# 3-1.net
KiCad netlist of a schematic drawn in Altium Designer
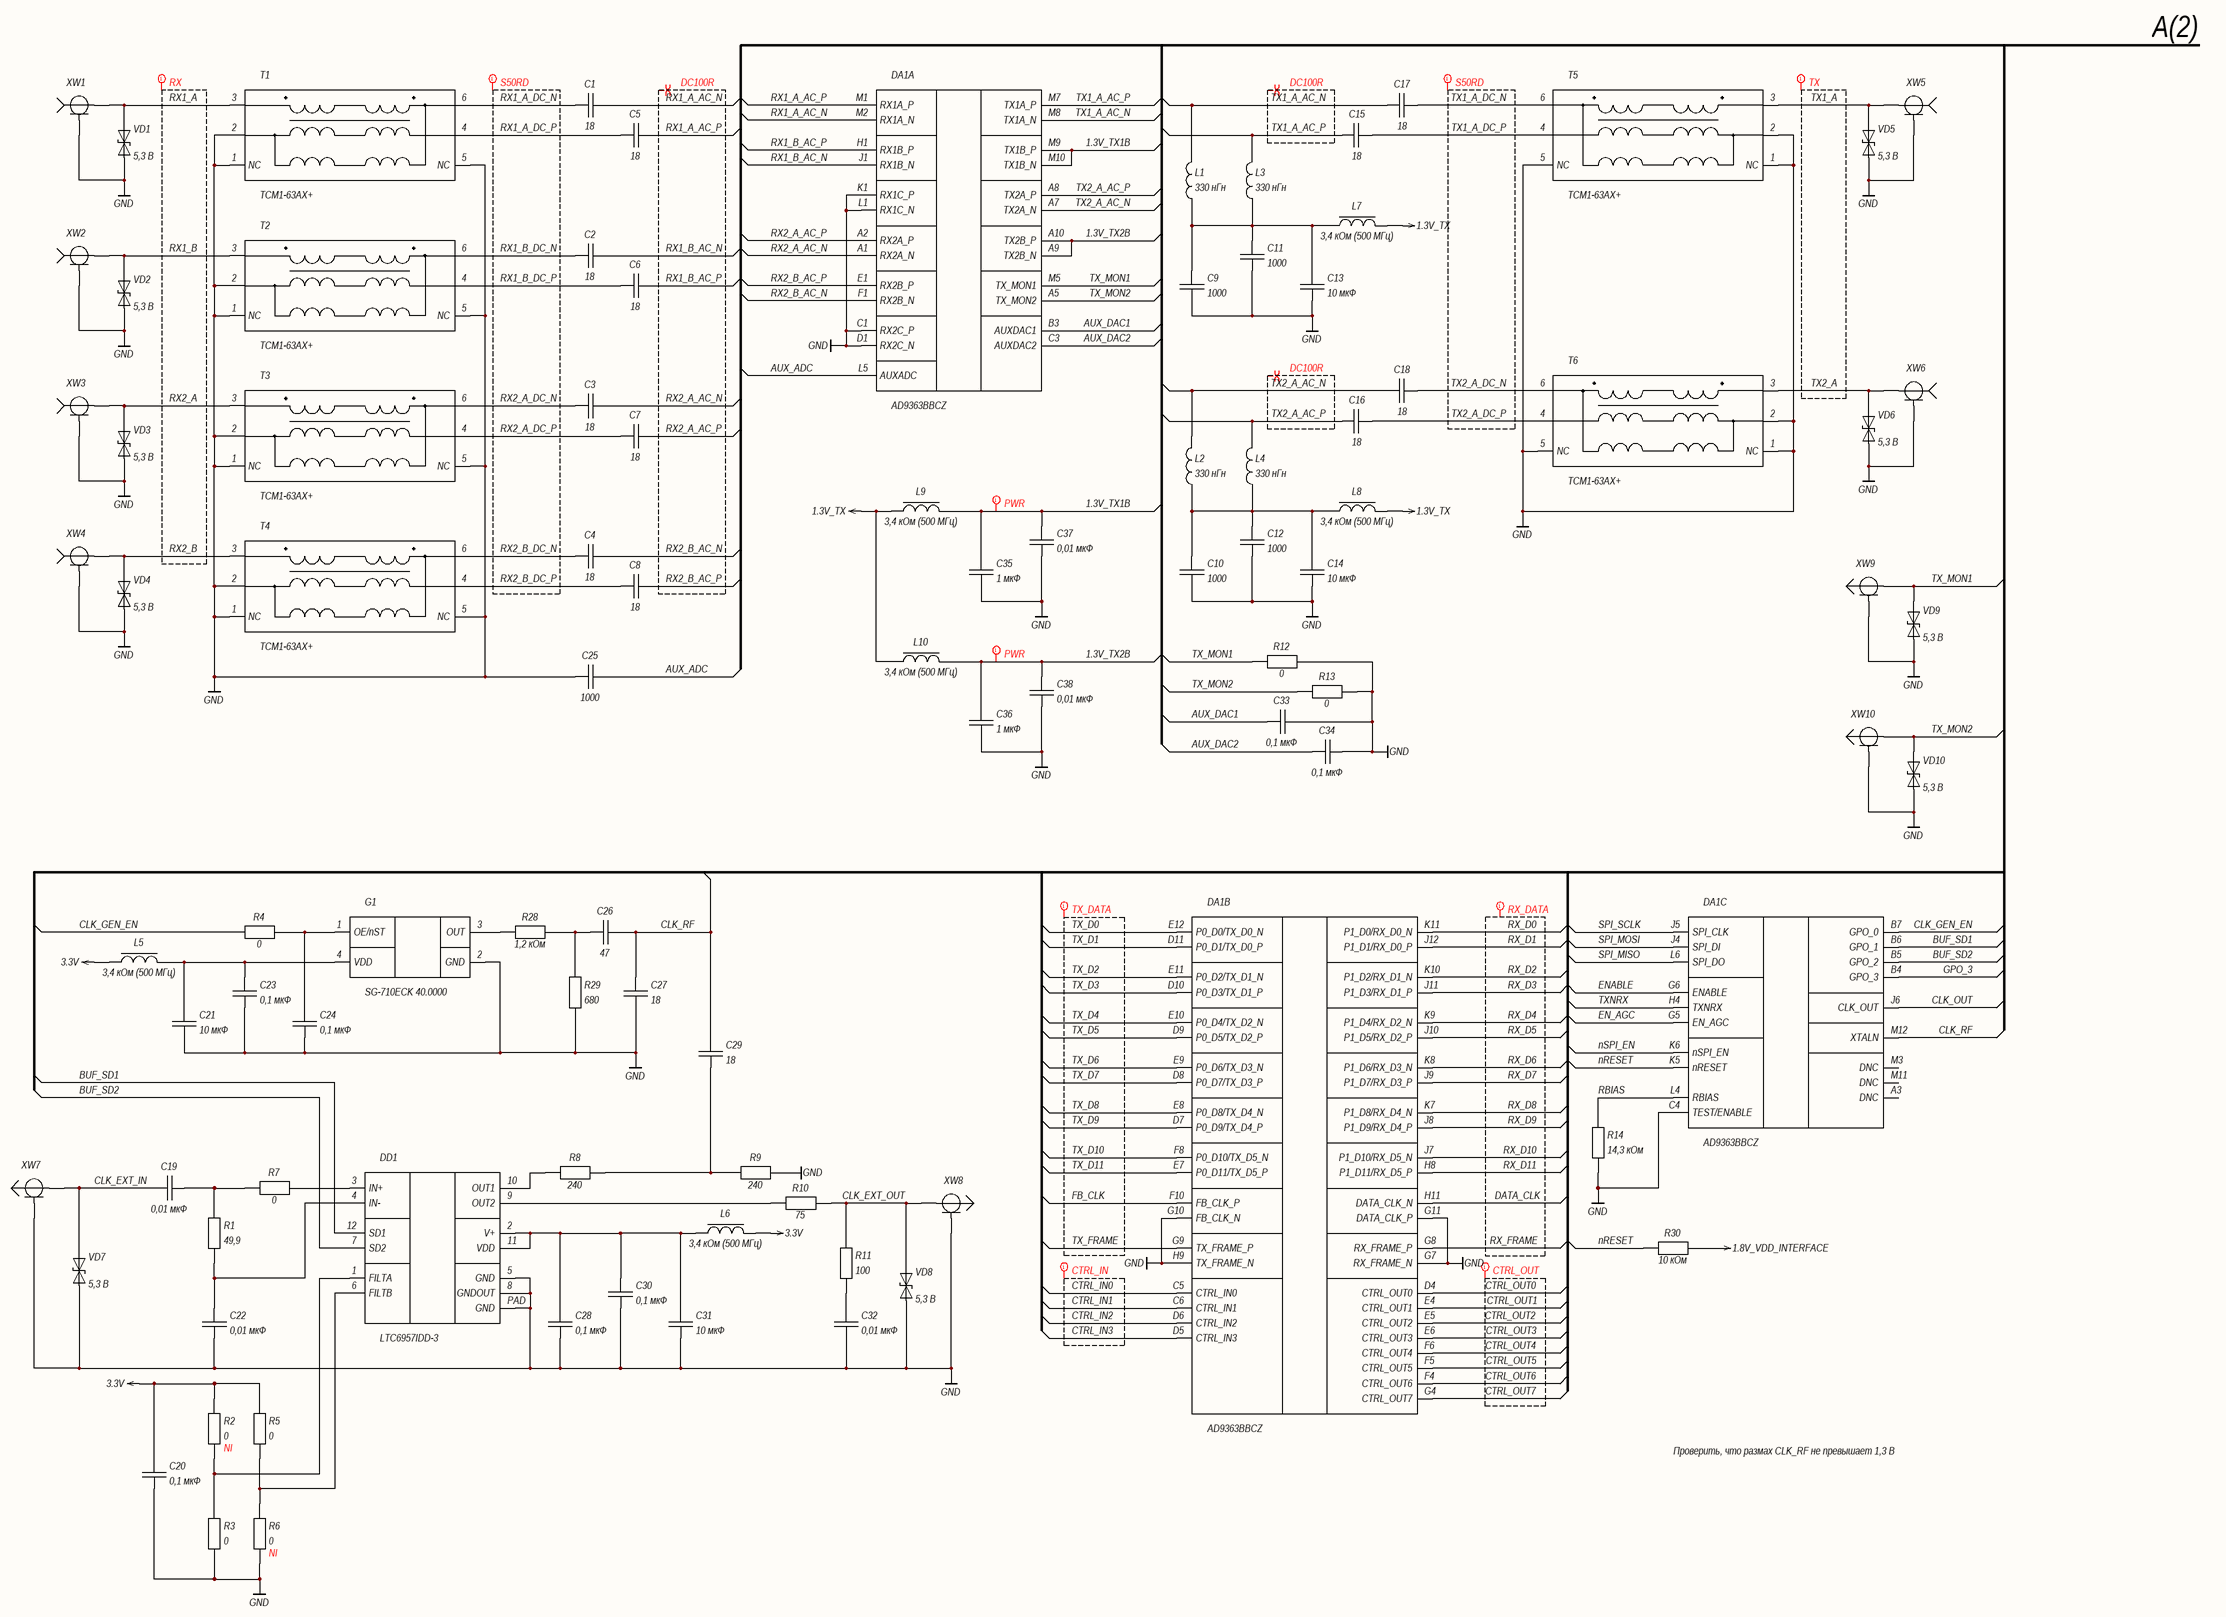
[diagram p0: Э3-1.SchDoc]

(export (version "E")
  (design (tool "Eeschema 10.0.6"))
  (components
    (comp (ref "C1")
      (value "18")
      (footprint "C0201-B-0.3mm-NO")
      (description "0201 18 пФ ±5% 50 В C0G")
      (fields (field (name "PARTNUMBER") "GRM0335C1H180JA01D"))
      (libsource (lib "Capacitors") (part "Non Polar Hor."))
    )
    (comp (ref "C2")
      (value "18")
      (footprint "C0201-B-0.3mm-NO")
      (description "0201 18 пФ ±5% 50 В C0G")
      (fields (field (name "PARTNUMBER") "GRM0335C1H180JA01D"))
      (libsource (lib "Capacitors") (part "Non Polar Hor."))
    )
    (comp (ref "C3")
      (value "18")
      (footprint "C0201-B-0.3mm-NO")
      (description "0201 18 пФ ±5% 50 В C0G")
      (fields (field (name "PARTNUMBER") "GRM0335C1H180JA01D"))
      (libsource (lib "Capacitors") (part "Non Polar Hor."))
    )
    (comp (ref "C4")
      (value "18")
      (footprint "C0201-B-0.3mm-NO")
      (description "0201 18 пФ ±5% 50 В C0G")
      (fields (field (name "PARTNUMBER") "GRM0335C1H180JA01D"))
      (libsource (lib "Capacitors") (part "Non Polar Hor."))
    )
    (comp (ref "C5")
      (value "18")
      (footprint "C0201-B-0.3mm-NO")
      (description "0201 18 пФ ±5% 50 В C0G")
      (fields (field (name "PARTNUMBER") "GRM0335C1H180JA01D"))
      (libsource (lib "Capacitors") (part "Non Polar Hor."))
    )
    (comp (ref "C6")
      (value "18")
      (footprint "C0201-B-0.3mm-NO")
      (description "0201 18 пФ ±5% 50 В C0G")
      (fields (field (name "PARTNUMBER") "GRM0335C1H180JA01D"))
      (libsource (lib "Capacitors") (part "Non Polar Hor."))
    )
    (comp (ref "C7")
      (value "18")
      (footprint "C0201-B-0.3mm-NO")
      (description "0201 18 пФ ±5% 50 В C0G")
      (fields (field (name "PARTNUMBER") "GRM0335C1H180JA01D"))
      (libsource (lib "Capacitors") (part "Non Polar Hor."))
    )
    (comp (ref "C8")
      (value "18")
      (footprint "C0201-B-0.3mm-NO")
      (description "0201 18 пФ ±5% 50 В C0G")
      (fields (field (name "PARTNUMBER") "GRM0335C1H180JA01D"))
      (libsource (lib "Capacitors") (part "Non Polar Hor."))
    )
    (comp (ref "C9")
      (value "1000")
      (footprint "C0201-B-0.3mm-NO")
      (description "0201 1000 пФ ±10% 16 В X7R")
      (libsource (lib "Capacitors") (part "Non Polar Ver."))
    )
    (comp (ref "C10")
      (value "1000")
      (footprint "C0201-B-0.3mm-NO")
      (description "0201 1000 пФ ±10% 16 В X7R")
      (libsource (lib "Capacitors") (part "Non Polar Ver."))
    )
    (comp (ref "C11")
      (value "1000")
      (footprint "C0201-B-0.3mm-NO")
      (description "0201 1000 пФ ±10% 16 В X7R")
      (libsource (lib "Capacitors") (part "Non Polar Ver."))
    )
    (comp (ref "C12")
      (value "1000")
      (footprint "C0201-B-0.3mm-NO")
      (description "0201 1000 пФ ±10% 16 В X7R")
      (libsource (lib "Capacitors") (part "Non Polar Ver."))
    )
    (comp (ref "C13")
      (value "10 мкФ")
      (footprint "C0603-B-0.8mm-NO")
      (description "0603 10 мкФ ±10% 16 В X7R")
      (libsource (lib "Capacitors") (part "Non Polar Ver."))
    )
    (comp (ref "C14")
      (value "10 мкФ")
      (footprint "C0603-B-0.8mm-NO")
      (description "0603 10 мкФ ±10% 16 В X7R")
      (libsource (lib "Capacitors") (part "Non Polar Ver."))
    )
    (comp (ref "C15")
      (value "18")
      (footprint "C0201-B-0.3mm-NO")
      (description "0201 18 пФ ±5% 50 В C0G")
      (fields (field (name "PARTNUMBER") "GRM0335C1H180JA01D"))
      (libsource (lib "Capacitors") (part "Non Polar Hor."))
    )
    (comp (ref "C16")
      (value "18")
      (footprint "C0201-B-0.3mm-NO")
      (description "0201 18 пФ ±5% 50 В C0G")
      (fields (field (name "PARTNUMBER") "GRM0335C1H180JA01D"))
      (libsource (lib "Capacitors") (part "Non Polar Hor."))
    )
    (comp (ref "C17")
      (value "18")
      (footprint "C0201-B-0.3mm-NO")
      (description "0201 18 пФ ±5% 50 В C0G")
      (fields (field (name "PARTNUMBER") "GRM0335C1H180JA01D"))
      (libsource (lib "Capacitors") (part "Non Polar Hor."))
    )
    (comp (ref "C18")
      (value "18")
      (footprint "C0201-B-0.3mm-NO")
      (description "0201 18 пФ ±5% 50 В C0G")
      (fields (field (name "PARTNUMBER") "GRM0335C1H180JA01D"))
      (libsource (lib "Capacitors") (part "Non Polar Hor."))
    )
    (comp (ref "C19")
      (value "0,01 мкФ")
      (footprint "C0201-B-0.3mm-NO")
      (description "0201 0,01 мкФ ±10% 16 В X7R")
      (fields (field (name "PARTNUMBER") "GRM0335C1H180JA01D"))
      (libsource (lib "Capacitors") (part "Non Polar Hor."))
    )
    (comp (ref "C20")
      (value "0,1 мкФ")
      (footprint "C0402-B-0.5mm-NO")
      (description "0402 0,1 мкФ ±10% 16 В X7R")
      (libsource (lib "Capacitors") (part "Non Polar Ver."))
    )
    (comp (ref "C21")
      (value "10 мкФ")
      (footprint "C0603-B-0.8mm-NO")
      (description "0603 10 мкФ ±10% 16 В X7R")
      (libsource (lib "Capacitors") (part "Non Polar Ver."))
    )
    (comp (ref "C22")
      (value "0,01 мкФ")
      (footprint "C0201-B-0.3mm-NO")
      (description "0201 0,01 мкФ ±10% 16 В X7R")
      (libsource (lib "Capacitors") (part "Non Polar Ver."))
    )
    (comp (ref "C23")
      (value "0,1 мкФ")
      (footprint "C0402-B-0.5mm-NO")
      (description "0402 0,1 мкФ ±10% 16 В X7R")
      (libsource (lib "Capacitors") (part "Non Polar Ver."))
    )
    (comp (ref "C24")
      (value "0,1 мкФ")
      (footprint "C0402-B-0.5mm-NO")
      (description "0402 0,1 мкФ ±10% 16 В X7R")
      (libsource (lib "Capacitors") (part "Non Polar Ver."))
    )
    (comp (ref "C25")
      (value "1000")
      (footprint "C0201-B-0.3mm-NO")
      (description "0201 1000 пФ ±10% 16 В X7R")
      (libsource (lib "Capacitors") (part "Non Polar Hor."))
    )
    (comp (ref "C26")
      (value "47")
      (footprint "C0402-B-0.5mm-NO")
      (description "0402 47 пФ ±5% 50 В X7R")
      (fields (field (name "PARTNUMBER") "GRM0335C1H180JA01D"))
      (libsource (lib "Capacitors") (part "Non Polar Hor."))
    )
    (comp (ref "C27")
      (value "18")
      (footprint "C0201-B-0.3mm-NO")
      (description "0201 18 пФ ±5% 50 В C0G")
      (libsource (lib "Capacitors") (part "Non Polar Ver."))
    )
    (comp (ref "C28")
      (value "0,1 мкФ")
      (footprint "C0402-B-0.5mm-NO")
      (description "0402 0,1 мкФ ±10% 16 В X7R")
      (libsource (lib "Capacitors") (part "Non Polar Ver."))
    )
    (comp (ref "C29")
      (value "18")
      (footprint "C0201-B-0.3mm-NO")
      (description "0201 18 пФ ±5% 50 В C0G")
      (libsource (lib "Capacitors") (part "Non Polar Ver."))
    )
    (comp (ref "C30")
      (value "0,1 мкФ")
      (footprint "C0402-B-0.5mm-NO")
      (description "0402 0,1 мкФ ±10% 16 В X7R")
      (libsource (lib "Capacitors") (part "Non Polar Ver."))
    )
    (comp (ref "C31")
      (value "10 мкФ")
      (footprint "C0603-B-0.8mm-NO")
      (description "0603 10 мкФ ±10% 16 В X7R")
      (libsource (lib "Capacitors") (part "Non Polar Ver."))
    )
    (comp (ref "C32")
      (value "0,01 мкФ")
      (footprint "C0201-B-0.3mm-NO")
      (description "0201 0,01 мкФ ±10% 16 В X7R")
      (libsource (lib "Capacitors") (part "Non Polar Ver."))
    )
    (comp (ref "C33")
      (value "0,1 мкФ")
      (footprint "C0201-B-0.3mm-NO")
      (description "0201 0,1 мкФ ±10% 16 В X7R")
      (libsource (lib "Capacitors") (part "Non Polar Hor."))
    )
    (comp (ref "C34")
      (value "0,1 мкФ")
      (footprint "C0201-B-0.3mm-NO")
      (description "0201 0,1 мкФ ±10% 16 В X7R")
      (libsource (lib "Capacitors") (part "Non Polar Hor."))
    )
    (comp (ref "C35")
      (value "1 мкФ")
      (footprint "C0402-B-0.5mm-NO")
      (description "0402 1 мкФ ±10% 16 В X7R")
      (libsource (lib "Capacitors") (part "Non Polar Ver."))
    )
    (comp (ref "C36")
      (value "1 мкФ")
      (footprint "C0402-B-0.5mm-NO")
      (description "0402 1 мкФ ±10% 16 В X7R")
      (libsource (lib "Capacitors") (part "Non Polar Ver."))
    )
    (comp (ref "C37")
      (value "0,01 мкФ")
      (footprint "C0201-B-0.3mm-NO")
      (description "0201 0,01 мкФ ±10% 16 В X7R")
      (libsource (lib "Capacitors") (part "Non Polar Ver."))
    )
    (comp (ref "C38")
      (value "0,01 мкФ")
      (footprint "C0201-B-0.3mm-NO")
      (description "0201 0,01 мкФ ±10% 16 В X7R")
      (libsource (lib "Capacitors") (part "Non Polar Ver."))
    )
    (comp (ref "DA1")
      (value "AD9363BBCZ")
      (footprint "144-BGA")
      (description "RF Agile Transceiver")
      (fields (field (name "MANUFACTURER") "AnalogDevices"))
      (libsource (lib "Analog") (part "AD9363"))
    )
    (comp (ref "DD1")
      (value "LTC6957IDD-3")
      (footprint "12-DFN")
      (fields (field (name "MANUFACTURER") "AnalogDevices"))
      (libsource (lib "Digital") (part "LTC6957IDD-3"))
    )
    (comp (ref "G1")
      (value "SG-710ECK 40.0000")
      (footprint "Generator 7x5x1.3")
      (fields (field (name "TOLERANCE") "± ppm"))
      (libsource (lib "Oscilators") (part "Generator"))
    )
    (comp (ref "L1")
      (value "330 нГн")
      (footprint "LCL0805-C-1.2mm-NO")
      (fields (field (name "PARTNUMBER") "L-15WR33GV4E"))
      (libsource (lib "Inductors") (part "Inductor Ver."))
    )
    (comp (ref "L2")
      (value "330 нГн")
      (footprint "LCL0805-C-1.2mm-NO")
      (fields (field (name "PARTNUMBER") "L-15WR33GV4E"))
      (libsource (lib "Inductors") (part "Inductor Ver."))
    )
    (comp (ref "L3")
      (value "330 нГн")
      (footprint "LCL0805-C-1.2mm-NO")
      (fields (field (name "PARTNUMBER") "L-15WR33GV4E"))
      (libsource (lib "Inductors") (part "Inductor Ver."))
    )
    (comp (ref "L4")
      (value "330 нГн")
      (footprint "LCL0805-C-1.2mm-NO")
      (fields (field (name "PARTNUMBER") "L-15WR33GV4E"))
      (libsource (lib "Inductors") (part "Inductor Ver."))
    )
    (comp (ref "L5")
      (value "3,4 кОм (500 МГц)")
      (footprint "L0402-B-0.5mm")
      (fields (field (name "PARTNUMBER") "BLM15HD182BH1"))
      (libsource (lib "Inductors") (part "Inductor MC Hor."))
    )
    (comp (ref "L6")
      (value "3,4 кОм (500 МГц)")
      (footprint "L0402-B-0.5mm")
      (fields (field (name "PARTNUMBER") "BLM15HD182BH1"))
      (libsource (lib "Inductors") (part "Inductor MC Hor."))
    )
    (comp (ref "L7")
      (value "3,4 кОм (500 МГц)")
      (footprint "L0402-B-0.5mm-NO")
      (fields (field (name "PARTNUMBER") "BLM15HD182BH1"))
      (libsource (lib "Inductors") (part "Inductor MC Hor."))
    )
    (comp (ref "L8")
      (value "3,4 кОм (500 МГц)")
      (footprint "L0402-B-0.5mm-NO")
      (fields (field (name "PARTNUMBER") "BLM15HD182BH1"))
      (libsource (lib "Inductors") (part "Inductor MC Hor."))
    )
    (comp (ref "L9")
      (value "3,4 кОм (500 МГц)")
      (footprint "L0402-B-0.5mm-NO")
      (fields (field (name "PARTNUMBER") "BLM15HD182BH1"))
      (libsource (lib "Inductors") (part "Inductor MC Hor."))
    )
    (comp (ref "L10")
      (value "3,4 кОм (500 МГц)")
      (footprint "L0402-B-0.5mm-NO")
      (fields (field (name "PARTNUMBER") "BLM15HD182BH1"))
      (libsource (lib "Inductors") (part "Inductor MC Hor."))
    )
    (comp (ref "R1")
      (value "49,9")
      (footprint "CR0402-B-0.35mm-NO")
      (description "0402 49,9 Ом 1%")
      (libsource (lib "Resistors") (part "Resistor Ver."))
    )
    (comp (ref "R2")
      (value "0")
      (footprint "CR0402-B-0.35mm-NO")
      (description "0402 0 Ом")
      (fields (field (name "COMPONENTTYPE") "NI"))
      (libsource (lib "Resistors") (part "Resistor Ver."))
    )
    (comp (ref "R3")
      (value "0")
      (footprint "CR0402-B-0.35mm-NO")
      (description "0402 0 Ом")
      (libsource (lib "Resistors") (part "Resistor Ver."))
    )
    (comp (ref "R4")
      (value "0")
      (footprint "CR0402-B-0.35mm-NO")
      (description "0402 0 Ом")
      (libsource (lib "Resistors") (part "Resistor Hor."))
    )
    (comp (ref "R5")
      (value "0")
      (footprint "CR0402-B-0.35mm-NO")
      (description "0402 0 Ом")
      (libsource (lib "Resistors") (part "Resistor Ver."))
    )
    (comp (ref "R6")
      (value "0")
      (footprint "CR0402-B-0.35mm-NO")
      (description "0402 0 Ом")
      (fields (field (name "COMPONENTTYPE") "NI"))
      (libsource (lib "Resistors") (part "Resistor Ver."))
    )
    (comp (ref "R7")
      (value "0")
      (footprint "CR0402-B-0.35mm-NO")
      (description "0402 0 Ом")
      (libsource (lib "Resistors") (part "Resistor Hor."))
    )
    (comp (ref "R8")
      (value "240")
      (footprint "CR0402-B-0.35mm-NO")
      (description "0402 240 Ом ±1%")
      (libsource (lib "Resistors") (part "Resistor Hor."))
    )
    (comp (ref "R9")
      (value "240")
      (footprint "CR0402-B-0.35mm-NO")
      (description "0402 240 Ом ±1%")
      (libsource (lib "Resistors") (part "Resistor Hor."))
    )
    (comp (ref "R10")
      (value "75")
      (footprint "CR0402-B-0.35mm-NO")
      (description "0402 75 Ом ±1%")
      (libsource (lib "Resistors") (part "Resistor Hor."))
    )
    (comp (ref "R11")
      (value "100")
      (footprint "CR0402-B-0.35mm-NO")
      (description "0402 100 Ом ±1%")
      (libsource (lib "Resistors") (part "Resistor Ver."))
    )
    (comp (ref "R12")
      (value "0")
      (footprint "CR0402-B-0.35mm-NO")
      (description "0402 0 Ом")
      (libsource (lib "Resistors") (part "Resistor Hor."))
    )
    (comp (ref "R13")
      (value "0")
      (footprint "CR0402-B-0.35mm-NO")
      (description "0402 0 Ом")
      (libsource (lib "Resistors") (part "Resistor Hor."))
    )
    (comp (ref "R14")
      (value "14,3 кОм")
      (footprint "CR0402-B-0.35mm-NO")
      (description "0402 14,3 кОм ±1%")
      (libsource (lib "Resistors") (part "Resistor Ver."))
    )
    (comp (ref "R28")
      (value "1,2 кОм")
      (footprint "CR0402-B-0.35mm-NO")
      (description "0402 1,2 кОм ±1%")
      (libsource (lib "Resistors") (part "Resistor Hor."))
    )
    (comp (ref "R29")
      (value "680")
      (footprint "CR0402-B-0.35mm-NO")
      (description "0402 680 Ом ±1%")
      (libsource (lib "Resistors") (part "Resistor Ver."))
    )
    (comp (ref "R30")
      (value "10 кОм")
      (footprint "CR0402-B-0.35mm-NO")
      (description "0402 10 кОм ±5%")
      (libsource (lib "Resistors") (part "Resistor Hor."))
    )
    (comp (ref "T1")
      (value "TCM1-63AX+")
      (footprint "TCM1-63AX+")
      (fields (field (name "PARTNUMBER") "TCM1-63AX+"))
      (libsource (lib "") (part "TCM1-63AX+_1"))
    )
    (comp (ref "T2")
      (value "TCM1-63AX+")
      (footprint "TCM1-63AX+")
      (fields (field (name "PARTNUMBER") "TCM1-63AX+"))
      (libsource (lib "") (part "TCM1-63AX+_1"))
    )
    (comp (ref "T3")
      (value "TCM1-63AX+")
      (footprint "TCM1-63AX+")
      (fields (field (name "PARTNUMBER") "TCM1-63AX+"))
      (libsource (lib "") (part "TCM1-63AX+_1"))
    )
    (comp (ref "T4")
      (value "TCM1-63AX+")
      (footprint "TCM1-63AX+")
      (fields (field (name "PARTNUMBER") "TCM1-63AX+"))
      (libsource (lib "") (part "TCM1-63AX+_1"))
    )
    (comp (ref "T5")
      (value "TCM1-63AX+")
      (footprint "TCM1-63AX+")
      (fields (field (name "PARTNUMBER") "TCM1-63AX+"))
      (libsource (lib "Inductors") (part "TCM1-63AX+"))
    )
    (comp (ref "T6")
      (value "TCM1-63AX+")
      (footprint "TCM1-63AX+")
      (fields (field (name "PARTNUMBER") "TCM1-63AX+"))
      (libsource (lib "Inductors") (part "TCM1-63AX+"))
    )
    (comp (ref "VD1")
      (value "~")
      (footprint "X3DFN2-NO")
      (fields (field (name "VOLTAGE") "5,3 В") (field (name "PARTNUMBER") "ESD8472MUT5G"))
      (libsource (lib "Diodes") (part "TVS Ver."))
    )
    (comp (ref "VD2")
      (value "~")
      (footprint "X3DFN2-NO")
      (fields (field (name "VOLTAGE") "5,3 В") (field (name "PARTNUMBER") "ESD8472MUT5G"))
      (libsource (lib "Diodes") (part "TVS Ver."))
    )
    (comp (ref "VD3")
      (value "~")
      (footprint "X3DFN2-NO")
      (fields (field (name "VOLTAGE") "5,3 В") (field (name "PARTNUMBER") "ESD8472MUT5G"))
      (libsource (lib "Diodes") (part "TVS Ver."))
    )
    (comp (ref "VD4")
      (value "~")
      (footprint "X3DFN2-NO")
      (fields (field (name "VOLTAGE") "5,3 В") (field (name "PARTNUMBER") "ESD8472MUT5G"))
      (libsource (lib "Diodes") (part "TVS Ver."))
    )
    (comp (ref "VD5")
      (value "~")
      (footprint "X3DFN2-NO")
      (fields (field (name "VOLTAGE") "5,3 В") (field (name "PARTNUMBER") "ESD8472MUT5G"))
      (libsource (lib "Diodes") (part "TVS Ver."))
    )
    (comp (ref "VD6")
      (value "~")
      (footprint "X3DFN2-NO")
      (fields (field (name "VOLTAGE") "5,3 В") (field (name "PARTNUMBER") "ESD8472MUT5G"))
      (libsource (lib "Diodes") (part "TVS Ver."))
    )
    (comp (ref "VD7")
      (value "~")
      (footprint "X3DFN2-NO")
      (fields (field (name "VOLTAGE") "5,3 В") (field (name "PARTNUMBER") "ESD8472MUT5G"))
      (libsource (lib "Diodes") (part "TVS Ver."))
    )
    (comp (ref "VD8")
      (value "~")
      (footprint "X3DFN2-NO")
      (fields (field (name "VOLTAGE") "5,3 В") (field (name "PARTNUMBER") "ESD8472MUT5G"))
      (libsource (lib "Diodes") (part "TVS Ver."))
    )
    (comp (ref "VD9")
      (value "~")
      (footprint "X3DFN2-NO")
      (fields (field (name "VOLTAGE") "5,3 В") (field (name "PARTNUMBER") "ESD8472MUT5G"))
      (libsource (lib "Diodes") (part "TVS Ver."))
    )
    (comp (ref "VD10")
      (value "~")
      (footprint "X3DFN2-NO")
      (fields (field (name "VOLTAGE") "5,3 В") (field (name "PARTNUMBER") "ESD8472MUT5G"))
      (libsource (lib "Diodes") (part "TVS Ver."))
    )
    (comp (ref "XW1")
      (value "XW(S)")
      (footprint "SMA-J-P-H-ST-EM1")
      (libsource (lib "Connectors") (part "XW(S)"))
    )
    (comp (ref "XW2")
      (value "XW(S)")
      (footprint "SMA-J-P-H-ST-EM1")
      (libsource (lib "Connectors") (part "XW(S)"))
    )
    (comp (ref "XW3")
      (value "XW(S)")
      (footprint "SMA-J-P-H-ST-EM1")
      (libsource (lib "Connectors") (part "XW(S)"))
    )
    (comp (ref "XW4")
      (value "XW(S)")
      (footprint "SMA-J-P-H-ST-EM1")
      (libsource (lib "Connectors") (part "XW(S)"))
    )
    (comp (ref "XW5")
      (value "XW(S)")
      (footprint "SMA-J-P-H-ST-EM1")
      (libsource (lib "Connectors") (part "XW(S)"))
    )
    (comp (ref "XW6")
      (value "XW(S)")
      (footprint "SMA-J-P-H-ST-EM1")
      (libsource (lib "Connectors") (part "XW(S)"))
    )
    (comp (ref "XW7")
      (value "XW(P)")
      (footprint "U.FL STR PLG")
      (libsource (lib "Connectors") (part "XW(P)"))
    )
    (comp (ref "XW8")
      (value "XW(P)")
      (footprint "U.FL STR PLG")
      (libsource (lib "Connectors") (part "XW(P)"))
    )
    (comp (ref "XW9")
      (value "XW(P)")
      (footprint "U.FL STR PLG")
      (libsource (lib "Connectors") (part "XW(P)"))
    )
    (comp (ref "XW10")
      (value "XW(P)")
      (footprint "U.FL STR PLG")
      (libsource (lib "Connectors") (part "XW(P)"))
    )
  )
  (nets
    (net (code "1") (name "/1.3V_TX1B") (class "Default")
      (node (ref "C35") (pin "1") (pinfunction "1_1") (pintype "passive"))
      (node (ref "C37") (pin "1") (pinfunction "1_1") (pintype "passive"))
      (node (ref "DA1") (pin "M10") (pinfunction "TX1B_N_M10") (pintype "passive"))
      (node (ref "DA1") (pin "M9") (pinfunction "TX1B_P_M9") (pintype "passive"))
      (node (ref "L9") (pin "2") (pinfunction "2_2") (pintype "passive"))
    )
    (net (code "2") (name "/1.3V_TX2B") (class "Default")
      (node (ref "C36") (pin "1") (pinfunction "1_1") (pintype "passive"))
      (node (ref "C38") (pin "1") (pinfunction "1_1") (pintype "passive"))
      (node (ref "DA1") (pin "A10") (pinfunction "TX2B_P_A10") (pintype "passive"))
      (node (ref "DA1") (pin "A9") (pinfunction "TX2B_N_A9") (pintype "passive"))
      (node (ref "L10") (pin "2") (pinfunction "2_2") (pintype "passive"))
    )
    (net (code "3") (name "/AUX_ADC") (class "Default")
      (node (ref "C25") (pin "2") (pinfunction "2_2") (pintype "passive"))
      (node (ref "DA1") (pin "L5") (pinfunction "AUXADC_L5") (pintype "passive"))
    )
    (net (code "4") (name "/AUX_DAC1") (class "Default")
      (node (ref "C33") (pin "1") (pinfunction "1_1") (pintype "passive"))
      (node (ref "DA1") (pin "B3") (pinfunction "AUXDAC1_B3") (pintype "passive"))
    )
    (net (code "5") (name "/AUX_DAC2") (class "Default")
      (node (ref "C34") (pin "1") (pinfunction "1_1") (pintype "passive"))
      (node (ref "DA1") (pin "C3") (pinfunction "AUXDAC2_C3") (pintype "passive"))
    )
    (net (code "6") (name "/BUF_SD1") (class "Default")
      (node (ref "DA1") (pin "B6") (pinfunction "GPO_1_B6") (pintype "passive"))
      (node (ref "DD1") (pin "12") (pinfunction "SD1_12") (pintype "passive"))
    )
    (net (code "7") (name "/BUF_SD2") (class "Default")
      (node (ref "DA1") (pin "B5") (pinfunction "GPO_2_B5") (pintype "passive"))
      (node (ref "DD1") (pin "7") (pinfunction "SD2_7") (pintype "passive"))
    )
    (net (code "8") (name "/CLK_EXT_IN") (class "Default")
      (node (ref "C19") (pin "1") (pinfunction "1_1") (pintype "passive"))
      (node (ref "VD7") (pin "1") (pinfunction "1_1") (pintype "passive"))
      (node (ref "XW7") (pin "1") (pinfunction "1_1") (pintype "passive"))
    )
    (net (code "9") (name "/CLK_EXT_OUT") (class "Default")
      (node (ref "R10") (pin "2") (pinfunction "2_2") (pintype "passive"))
      (node (ref "R11") (pin "1") (pinfunction "1_1") (pintype "passive"))
      (node (ref "VD8") (pin "1") (pinfunction "1_1") (pintype "passive"))
      (node (ref "XW8") (pin "1") (pinfunction "1_1") (pintype "passive"))
    )
    (net (code "10") (name "/CLK_GEN_EN") (class "Default")
      (node (ref "DA1") (pin "B7") (pinfunction "GPO_0_B7") (pintype "passive"))
      (node (ref "R4") (pin "1") (pinfunction "1_1") (pintype "passive"))
    )
    (net (code "11") (name "/CLK_OUT") (class "Default")
      (node (ref "DA1") (pin "J6") (pinfunction "CLK_OUT_J6") (pintype "passive"))
    )
    (net (code "12") (name "/CLK_RF") (class "Default")
      (node (ref "C26") (pin "2") (pinfunction "2_2") (pintype "passive"))
      (node (ref "C27") (pin "1") (pinfunction "1_1") (pintype "passive"))
      (node (ref "C29") (pin "1") (pinfunction "1_1") (pintype "passive"))
      (node (ref "DA1") (pin "M12") (pinfunction "XTALN_M12") (pintype "passive"))
    )
    (net (code "13") (name "/CTRL_IN0") (class "Default")
      (node (ref "DA1") (pin "C5") (pinfunction "CTRL_IN0_C5") (pintype "passive"))
    )
    (net (code "14") (name "/CTRL_IN1") (class "Default")
      (node (ref "DA1") (pin "C6") (pinfunction "CTRL_IN1_C6") (pintype "passive"))
    )
    (net (code "15") (name "/CTRL_IN2") (class "Default")
      (node (ref "DA1") (pin "D6") (pinfunction "CTRL_IN2_D6") (pintype "passive"))
    )
    (net (code "16") (name "/CTRL_IN3") (class "Default")
      (node (ref "DA1") (pin "D5") (pinfunction "CTRL_IN3_D5") (pintype "passive"))
    )
    (net (code "17") (name "/CTRL_OUT0") (class "Default")
      (node (ref "DA1") (pin "D4") (pinfunction "CTRL_OUT0_D4") (pintype "passive"))
    )
    (net (code "18") (name "/CTRL_OUT1") (class "Default")
      (node (ref "DA1") (pin "E4") (pinfunction "CTRL_OUT1_E4") (pintype "passive"))
    )
    (net (code "19") (name "/CTRL_OUT2") (class "Default")
      (node (ref "DA1") (pin "E5") (pinfunction "CTRL_OUT2_E5") (pintype "passive"))
    )
    (net (code "20") (name "/CTRL_OUT3") (class "Default")
      (node (ref "DA1") (pin "E6") (pinfunction "CTRL_OUT3_E6") (pintype "passive"))
    )
    (net (code "21") (name "/CTRL_OUT4") (class "Default")
      (node (ref "DA1") (pin "F6") (pinfunction "CTRL_OUT4_F6") (pintype "passive"))
    )
    (net (code "22") (name "/CTRL_OUT5") (class "Default")
      (node (ref "DA1") (pin "F5") (pinfunction "CTRL_OUT5_F5") (pintype "passive"))
    )
    (net (code "23") (name "/CTRL_OUT6") (class "Default")
      (node (ref "DA1") (pin "F4") (pinfunction "CTRL_OUT6_F4") (pintype "passive"))
    )
    (net (code "24") (name "/CTRL_OUT7") (class "Default")
      (node (ref "DA1") (pin "G4") (pinfunction "CTRL_OUT7_G4") (pintype "passive"))
    )
    (net (code "25") (name "/DATA_CLK") (class "Default")
      (node (ref "DA1") (pin "H11") (pinfunction "DATA_CLK_N_H11") (pintype "passive"))
    )
    (net (code "26") (name "/ENABLE") (class "Default")
      (node (ref "DA1") (pin "G6") (pinfunction "ENABLE_G6") (pintype "passive"))
    )
    (net (code "27") (name "/EN_AGC") (class "Default")
      (node (ref "DA1") (pin "G5") (pinfunction "EN_AGC_G5") (pintype "passive"))
    )
    (net (code "28") (name "/FB_CLK") (class "Default")
      (node (ref "DA1") (pin "F10") (pinfunction "FB_CLK_P_F10") (pintype "passive"))
    )
    (net (code "29") (name "/GPO_3") (class "Default")
      (node (ref "DA1") (pin "B4") (pinfunction "GPO_3_B4") (pintype "passive"))
    )
    (net (code "30") (name "/RBIAS") (class "Default")
      (node (ref "DA1") (pin "L4") (pinfunction "RBIAS_L4") (pintype "passive"))
      (node (ref "R14") (pin "1") (pinfunction "1_1") (pintype "passive"))
    )
    (net (code "31") (name "/RX1_A") (class "Default")
      (node (ref "T1") (pin "3") (pinfunction "3_3") (pintype "passive"))
      (node (ref "VD1") (pin "1") (pinfunction "1_1") (pintype "passive"))
      (node (ref "XW1") (pin "1") (pinfunction "1_1") (pintype "passive"))
    )
    (net (code "32") (name "/RX1_A_AC_N") (class "Default")
      (node (ref "C1") (pin "2") (pinfunction "2_2") (pintype "passive"))
      (node (ref "DA1") (pin "M2") (pinfunction "RX1A_N_M2") (pintype "passive"))
    )
    (net (code "33") (name "/RX1_A_AC_P") (class "Default")
      (node (ref "C5") (pin "2") (pinfunction "2_2") (pintype "passive"))
      (node (ref "DA1") (pin "M1") (pinfunction "RX1A_P_M1") (pintype "passive"))
    )
    (net (code "34") (name "/RX1_A_DC_N") (class "Default")
      (node (ref "C1") (pin "1") (pinfunction "1_1") (pintype "passive"))
      (node (ref "T1") (pin "6") (pinfunction "6_6") (pintype "passive"))
    )
    (net (code "35") (name "/RX1_A_DC_P") (class "Default")
      (node (ref "C5") (pin "1") (pinfunction "1_1") (pintype "passive"))
      (node (ref "T1") (pin "4") (pinfunction "4_4") (pintype "passive"))
    )
    (net (code "36") (name "/RX1_B") (class "Default")
      (node (ref "T2") (pin "3") (pinfunction "3_3") (pintype "passive"))
      (node (ref "VD2") (pin "1") (pinfunction "1_1") (pintype "passive"))
      (node (ref "XW2") (pin "1") (pinfunction "1_1") (pintype "passive"))
    )
    (net (code "37") (name "/RX1_B_AC_N") (class "Default")
      (node (ref "C2") (pin "2") (pinfunction "2_2") (pintype "passive"))
      (node (ref "DA1") (pin "J1") (pinfunction "RX1B_N_J1") (pintype "passive"))
    )
    (net (code "38") (name "/RX1_B_AC_P") (class "Default")
      (node (ref "C6") (pin "2") (pinfunction "2_2") (pintype "passive"))
      (node (ref "DA1") (pin "H1") (pinfunction "RX1B_P_H1") (pintype "passive"))
    )
    (net (code "39") (name "/RX1_B_DC_N") (class "Default")
      (node (ref "C2") (pin "1") (pinfunction "1_1") (pintype "passive"))
      (node (ref "T2") (pin "6") (pinfunction "6_6") (pintype "passive"))
    )
    (net (code "40") (name "/RX1_B_DC_P") (class "Default")
      (node (ref "C6") (pin "1") (pinfunction "1_1") (pintype "passive"))
      (node (ref "T2") (pin "4") (pinfunction "4_4") (pintype "passive"))
    )
    (net (code "41") (name "/RX2_A") (class "Default")
      (node (ref "T3") (pin "3") (pinfunction "3_3") (pintype "passive"))
      (node (ref "VD3") (pin "1") (pinfunction "1_1") (pintype "passive"))
      (node (ref "XW3") (pin "1") (pinfunction "1_1") (pintype "passive"))
    )
    (net (code "42") (name "/RX2_A_AC_N") (class "Default")
      (node (ref "C3") (pin "2") (pinfunction "2_2") (pintype "passive"))
      (node (ref "DA1") (pin "A1") (pinfunction "RX2A_N_A1") (pintype "passive"))
    )
    (net (code "43") (name "/RX2_A_AC_P") (class "Default")
      (node (ref "C7") (pin "2") (pinfunction "2_2") (pintype "passive"))
      (node (ref "DA1") (pin "A2") (pinfunction "RX2A_P_A2") (pintype "passive"))
    )
    (net (code "44") (name "/RX2_A_DC_N") (class "Default")
      (node (ref "C3") (pin "1") (pinfunction "1_1") (pintype "passive"))
      (node (ref "T3") (pin "6") (pinfunction "6_6") (pintype "passive"))
    )
    (net (code "45") (name "/RX2_A_DC_P") (class "Default")
      (node (ref "C7") (pin "1") (pinfunction "1_1") (pintype "passive"))
      (node (ref "T3") (pin "4") (pinfunction "4_4") (pintype "passive"))
    )
    (net (code "46") (name "/RX2_B") (class "Default")
      (node (ref "T4") (pin "3") (pinfunction "3_3") (pintype "passive"))
      (node (ref "VD4") (pin "1") (pinfunction "1_1") (pintype "passive"))
      (node (ref "XW4") (pin "1") (pinfunction "1_1") (pintype "passive"))
    )
    (net (code "47") (name "/RX2_B_AC_N") (class "Default")
      (node (ref "C4") (pin "2") (pinfunction "2_2") (pintype "passive"))
      (node (ref "DA1") (pin "F1") (pinfunction "RX2B_N_F1") (pintype "passive"))
    )
    (net (code "48") (name "/RX2_B_AC_P") (class "Default")
      (node (ref "C8") (pin "2") (pinfunction "2_2") (pintype "passive"))
      (node (ref "DA1") (pin "E1") (pinfunction "RX2B_P_E1") (pintype "passive"))
    )
    (net (code "49") (name "/RX2_B_DC_N") (class "Default")
      (node (ref "C4") (pin "1") (pinfunction "1_1") (pintype "passive"))
      (node (ref "T4") (pin "6") (pinfunction "6_6") (pintype "passive"))
    )
    (net (code "50") (name "/RX2_B_DC_P") (class "Default")
      (node (ref "C8") (pin "1") (pinfunction "1_1") (pintype "passive"))
      (node (ref "T4") (pin "4") (pinfunction "4_4") (pintype "passive"))
    )
    (net (code "51") (name "/RX_D0") (class "Default")
      (node (ref "DA1") (pin "K11") (pinfunction "P1_D0/RX_D0_N_K11") (pintype "passive"))
    )
    (net (code "52") (name "/RX_D1") (class "Default")
      (node (ref "DA1") (pin "J12") (pinfunction "P1_D1/RX_D0_P_J12") (pintype "passive"))
    )
    (net (code "53") (name "/RX_D2") (class "Default")
      (node (ref "DA1") (pin "K10") (pinfunction "P1_D2/RX_D1_N_K10") (pintype "passive"))
    )
    (net (code "54") (name "/RX_D3") (class "Default")
      (node (ref "DA1") (pin "J11") (pinfunction "P1_D3/RX_D1_P_J11") (pintype "passive"))
    )
    (net (code "55") (name "/RX_D4") (class "Default")
      (node (ref "DA1") (pin "K9") (pinfunction "P1_D4/RX_D2_N_K9") (pintype "passive"))
    )
    (net (code "56") (name "/RX_D5") (class "Default")
      (node (ref "DA1") (pin "J10") (pinfunction "P1_D5/RX_D2_P_J10") (pintype "passive"))
    )
    (net (code "57") (name "/RX_D6") (class "Default")
      (node (ref "DA1") (pin "K8") (pinfunction "P1_D6/RX_D3_N_K8") (pintype "passive"))
    )
    (net (code "58") (name "/RX_D7") (class "Default")
      (node (ref "DA1") (pin "J9") (pinfunction "P1_D7/RX_D3_P_J9") (pintype "passive"))
    )
    (net (code "59") (name "/RX_D8") (class "Default")
      (node (ref "DA1") (pin "K7") (pinfunction "P1_D8/RX_D4_N_K7") (pintype "passive"))
    )
    (net (code "60") (name "/RX_D9") (class "Default")
      (node (ref "DA1") (pin "J8") (pinfunction "P1_D9/RX_D4_P_J8") (pintype "passive"))
    )
    (net (code "61") (name "/RX_D10") (class "Default")
      (node (ref "DA1") (pin "J7") (pinfunction "P1_D10/RX_D5_N_J7") (pintype "passive"))
    )
    (net (code "62") (name "/RX_D11") (class "Default")
      (node (ref "DA1") (pin "H8") (pinfunction "P1_D11/RX_D5_P_H8") (pintype "passive"))
    )
    (net (code "63") (name "/RX_FRAME") (class "Default")
      (node (ref "DA1") (pin "G8") (pinfunction "RX_FRAME_P_G8") (pintype "passive"))
    )
    (net (code "64") (name "/SPI_MISO") (class "Default")
      (node (ref "DA1") (pin "L6") (pinfunction "SPI_DO_L6") (pintype "passive"))
    )
    (net (code "65") (name "/SPI_MOSI") (class "Default")
      (node (ref "DA1") (pin "J4") (pinfunction "SPI_DI_J4") (pintype "passive"))
    )
    (net (code "66") (name "/SPI_SCLK") (class "Default")
      (node (ref "DA1") (pin "J5") (pinfunction "SPI_CLK_J5") (pintype "passive"))
    )
    (net (code "67") (name "/TX1_A") (class "Default")
      (node (ref "T5") (pin "3") (pinfunction "3_3") (pintype "passive"))
      (node (ref "VD5") (pin "1") (pinfunction "1_1") (pintype "passive"))
      (node (ref "XW5") (pin "1") (pinfunction "1_1") (pintype "passive"))
    )
    (net (code "68") (name "/TX1_A_AC_N") (class "Default")
      (node (ref "C17") (pin "2") (pinfunction "2_2") (pintype "passive"))
      (node (ref "DA1") (pin "M8") (pinfunction "TX1A_N_M8") (pintype "passive"))
      (node (ref "L1") (pin "1") (pinfunction "1_1") (pintype "passive"))
    )
    (net (code "69") (name "/TX1_A_AC_P") (class "Default")
      (node (ref "C15") (pin "2") (pinfunction "2_2") (pintype "passive"))
      (node (ref "DA1") (pin "M7") (pinfunction "TX1A_P_M7") (pintype "passive"))
      (node (ref "L3") (pin "1") (pinfunction "1_1") (pintype "passive"))
    )
    (net (code "70") (name "/TX1_A_DC_N") (class "Default")
      (node (ref "C17") (pin "1") (pinfunction "1_1") (pintype "passive"))
      (node (ref "T5") (pin "6") (pinfunction "6_6") (pintype "passive"))
    )
    (net (code "71") (name "/TX1_A_DC_P") (class "Default")
      (node (ref "C15") (pin "1") (pinfunction "1_1") (pintype "passive"))
      (node (ref "T5") (pin "4") (pinfunction "4_4") (pintype "passive"))
    )
    (net (code "72") (name "/TX2_A") (class "Default")
      (node (ref "T6") (pin "3") (pinfunction "3_3") (pintype "passive"))
      (node (ref "VD6") (pin "1") (pinfunction "1_1") (pintype "passive"))
      (node (ref "XW6") (pin "1") (pinfunction "1_1") (pintype "passive"))
    )
    (net (code "73") (name "/TX2_A_AC_N") (class "Default")
      (node (ref "C18") (pin "2") (pinfunction "2_2") (pintype "passive"))
      (node (ref "DA1") (pin "A7") (pinfunction "TX2A_N_A7") (pintype "passive"))
      (node (ref "L2") (pin "1") (pinfunction "1_1") (pintype "passive"))
    )
    (net (code "74") (name "/TX2_A_AC_P") (class "Default")
      (node (ref "C16") (pin "2") (pinfunction "2_2") (pintype "passive"))
      (node (ref "DA1") (pin "A8") (pinfunction "TX2A_P_A8") (pintype "passive"))
      (node (ref "L4") (pin "1") (pinfunction "1_1") (pintype "passive"))
    )
    (net (code "75") (name "/TX2_A_DC_N") (class "Default")
      (node (ref "C18") (pin "1") (pinfunction "1_1") (pintype "passive"))
      (node (ref "T6") (pin "6") (pinfunction "6_6") (pintype "passive"))
    )
    (net (code "76") (name "/TX2_A_DC_P") (class "Default")
      (node (ref "C16") (pin "1") (pinfunction "1_1") (pintype "passive"))
      (node (ref "T6") (pin "4") (pinfunction "4_4") (pintype "passive"))
    )
    (net (code "77") (name "/TXNRX") (class "Default")
      (node (ref "DA1") (pin "H4") (pinfunction "TXNRX_H4") (pintype "passive"))
    )
    (net (code "78") (name "/TX_D0") (class "Default")
      (node (ref "DA1") (pin "E12") (pinfunction "P0_D0/TX_D0_N_E12") (pintype "passive"))
    )
    (net (code "79") (name "/TX_D1") (class "Default")
      (node (ref "DA1") (pin "D11") (pinfunction "P0_D1/TX_D0_P_D11") (pintype "passive"))
    )
    (net (code "80") (name "/TX_D2") (class "Default")
      (node (ref "DA1") (pin "E11") (pinfunction "P0_D2/TX_D1_N_E11") (pintype "passive"))
    )
    (net (code "81") (name "/TX_D3") (class "Default")
      (node (ref "DA1") (pin "D10") (pinfunction "P0_D3/TX_D1_P_D10") (pintype "passive"))
    )
    (net (code "82") (name "/TX_D4") (class "Default")
      (node (ref "DA1") (pin "E10") (pinfunction "P0_D4/TX_D2_N_E10") (pintype "passive"))
    )
    (net (code "83") (name "/TX_D5") (class "Default")
      (node (ref "DA1") (pin "D9") (pinfunction "P0_D5/TX_D2_P_D9") (pintype "passive"))
    )
    (net (code "84") (name "/TX_D6") (class "Default")
      (node (ref "DA1") (pin "E9") (pinfunction "P0_D6/TX_D3_N_E9") (pintype "passive"))
    )
    (net (code "85") (name "/TX_D7") (class "Default")
      (node (ref "DA1") (pin "D8") (pinfunction "P0_D7/TX_D3_P_D8") (pintype "passive"))
    )
    (net (code "86") (name "/TX_D8") (class "Default")
      (node (ref "DA1") (pin "E8") (pinfunction "P0_D8/TX_D4_N_E8") (pintype "passive"))
    )
    (net (code "87") (name "/TX_D9") (class "Default")
      (node (ref "DA1") (pin "D7") (pinfunction "P0_D9/TX_D4_P_D7") (pintype "passive"))
    )
    (net (code "88") (name "/TX_D10") (class "Default")
      (node (ref "DA1") (pin "F8") (pinfunction "P0_D10/TX_D5_N_F8") (pintype "passive"))
    )
    (net (code "89") (name "/TX_D11") (class "Default")
      (node (ref "DA1") (pin "E7") (pinfunction "P0_D11/TX_D5_P_E7") (pintype "passive"))
    )
    (net (code "90") (name "/TX_FRAME") (class "Default")
      (node (ref "DA1") (pin "G9") (pinfunction "TX_FRAME_P_G9") (pintype "passive"))
    )
    (net (code "91") (name "/TX_MON1") (class "Default")
      (node (ref "DA1") (pin "M5") (pinfunction "TX_MON1_M5") (pintype "passive"))
      (node (ref "R12") (pin "1") (pinfunction "1_1") (pintype "passive"))
      (node (ref "VD9") (pin "1") (pinfunction "1_1") (pintype "passive"))
      (node (ref "XW9") (pin "1") (pinfunction "1_1") (pintype "passive"))
    )
    (net (code "92") (name "/TX_MON2") (class "Default")
      (node (ref "DA1") (pin "A5") (pinfunction "TX_MON2_A5") (pintype "passive"))
      (node (ref "R13") (pin "1") (pinfunction "1_1") (pintype "passive"))
      (node (ref "VD10") (pin "1") (pinfunction "1_1") (pintype "passive"))
      (node (ref "XW10") (pin "1") (pinfunction "1_1") (pintype "passive"))
    )
    (net (code "93") (name "/nRESET") (class "Default")
      (node (ref "DA1") (pin "K5") (pinfunction "nRESET_K5") (pintype "passive"))
      (node (ref "R30") (pin "1") (pinfunction "1_1") (pintype "passive"))
    )
    (net (code "94") (name "/nSPI_EN") (class "Default")
      (node (ref "DA1") (pin "K6") (pinfunction "nSPI_EN_K6") (pintype "passive"))
    )
    (net (code "95") (name "1.3V_TX") (class "Default")
      (node (ref "L10") (pin "1") (pinfunction "1_1") (pintype "passive"))
      (node (ref "L7") (pin "2") (pinfunction "2_2") (pintype "passive"))
      (node (ref "L8") (pin "2") (pinfunction "2_2") (pintype "passive"))
      (node (ref "L9") (pin "1") (pinfunction "1_1") (pintype "passive"))
    )
    (net (code "96") (name "1.8V_VDD_INTERFACE") (class "Default")
      (node (ref "R30") (pin "2") (pinfunction "2_2") (pintype "passive"))
    )
    (net (code "97") (name "3.3V") (class "Default")
      (node (ref "C20") (pin "1") (pinfunction "1_1") (pintype "passive"))
      (node (ref "L5") (pin "1") (pinfunction "1_1") (pintype "passive"))
      (node (ref "L6") (pin "2") (pinfunction "2_2") (pintype "passive"))
      (node (ref "R2") (pin "1") (pinfunction "1_1") (pintype "passive"))
      (node (ref "R5") (pin "1") (pinfunction "1_1") (pintype "passive"))
    )
    (net (code "98") (name "GND") (class "Default")
      (node (ref "C10") (pin "2") (pinfunction "2_2") (pintype "passive"))
      (node (ref "C11") (pin "2") (pinfunction "2_2") (pintype "passive"))
      (node (ref "C12") (pin "2") (pinfunction "2_2") (pintype "passive"))
      (node (ref "C13") (pin "2") (pinfunction "2_2") (pintype "passive"))
      (node (ref "C14") (pin "2") (pinfunction "2_2") (pintype "passive"))
      (node (ref "C20") (pin "2") (pinfunction "2_2") (pintype "passive"))
      (node (ref "C21") (pin "2") (pinfunction "2_2") (pintype "passive"))
      (node (ref "C22") (pin "2") (pinfunction "2_2") (pintype "passive"))
      (node (ref "C23") (pin "2") (pinfunction "2_2") (pintype "passive"))
      (node (ref "C24") (pin "2") (pinfunction "2_2") (pintype "passive"))
      (node (ref "C25") (pin "1") (pinfunction "1_1") (pintype "passive"))
      (node (ref "C27") (pin "2") (pinfunction "2_2") (pintype "passive"))
      (node (ref "C28") (pin "2") (pinfunction "2_2") (pintype "passive"))
      (node (ref "C30") (pin "2") (pinfunction "2_2") (pintype "passive"))
      (node (ref "C31") (pin "2") (pinfunction "2_2") (pintype "passive"))
      (node (ref "C32") (pin "2") (pinfunction "2_2") (pintype "passive"))
      (node (ref "C33") (pin "2") (pinfunction "2_2") (pintype "passive"))
      (node (ref "C34") (pin "2") (pinfunction "2_2") (pintype "passive"))
      (node (ref "C35") (pin "2") (pinfunction "2_2") (pintype "passive"))
      (node (ref "C36") (pin "2") (pinfunction "2_2") (pintype "passive"))
      (node (ref "C37") (pin "2") (pinfunction "2_2") (pintype "passive"))
      (node (ref "C38") (pin "2") (pinfunction "2_2") (pintype "passive"))
      (node (ref "C9") (pin "2") (pinfunction "2_2") (pintype "passive"))
      (node (ref "DA1") (pin "C1") (pinfunction "RX2C_P_C1") (pintype "passive"))
      (node (ref "DA1") (pin "C4") (pinfunction "TEST/ENABLE_C4") (pintype "passive"))
      (node (ref "DA1") (pin "D1") (pinfunction "RX2C_N_D1") (pintype "passive"))
      (node (ref "DA1") (pin "G10") (pinfunction "FB_CLK_N_G10") (pintype "passive"))
      (node (ref "DA1") (pin "G11") (pinfunction "DATA_CLK_P_G11") (pintype "passive"))
      (node (ref "DA1") (pin "G7") (pinfunction "RX_FRAME_N_G7") (pintype "passive"))
      (node (ref "DA1") (pin "H9") (pinfunction "TX_FRAME_N_H9") (pintype "passive"))
      (node (ref "DA1") (pin "K1") (pinfunction "RX1C_P_K1") (pintype "passive"))
      (node (ref "DA1") (pin "L1") (pinfunction "RX1C_N_L1") (pintype "passive"))
      (node (ref "DD1") (pin "5") (pinfunction "GND_5") (pintype "passive"))
      (node (ref "DD1") (pin "8") (pinfunction "GNDOUT_8") (pintype "passive"))
      (node (ref "DD1") (pin "PAD") (pinfunction "GND_PAD") (pintype "passive"))
      (node (ref "G1") (pin "2") (pinfunction "GND_2") (pintype "passive"))
      (node (ref "R12") (pin "2") (pinfunction "2_2") (pintype "passive"))
      (node (ref "R13") (pin "2") (pinfunction "2_2") (pintype "passive"))
      (node (ref "R14") (pin "2") (pinfunction "2_2") (pintype "passive"))
      (node (ref "R29") (pin "2") (pinfunction "2_2") (pintype "passive"))
      (node (ref "R3") (pin "2") (pinfunction "2_2") (pintype "passive"))
      (node (ref "R6") (pin "2") (pinfunction "2_2") (pintype "passive"))
      (node (ref "R9") (pin "2") (pinfunction "2_2") (pintype "passive"))
      (node (ref "T1") (pin "1") (pinfunction "NC_1") (pintype "passive"))
      (node (ref "T1") (pin "2") (pinfunction "2_2") (pintype "passive"))
      (node (ref "T1") (pin "5") (pinfunction "NC_5") (pintype "passive"))
      (node (ref "T2") (pin "1") (pinfunction "NC_1") (pintype "passive"))
      (node (ref "T2") (pin "2") (pinfunction "2_2") (pintype "passive"))
      (node (ref "T2") (pin "5") (pinfunction "NC_5") (pintype "passive"))
      (node (ref "T3") (pin "1") (pinfunction "NC_1") (pintype "passive"))
      (node (ref "T3") (pin "2") (pinfunction "2_2") (pintype "passive"))
      (node (ref "T3") (pin "5") (pinfunction "NC_5") (pintype "passive"))
      (node (ref "T4") (pin "1") (pinfunction "NC_1") (pintype "passive"))
      (node (ref "T4") (pin "2") (pinfunction "2_2") (pintype "passive"))
      (node (ref "T4") (pin "5") (pinfunction "NC_5") (pintype "passive"))
      (node (ref "T5") (pin "1") (pinfunction "NC_1") (pintype "passive"))
      (node (ref "T5") (pin "2") (pinfunction "2_2") (pintype "passive"))
      (node (ref "T5") (pin "5") (pinfunction "NC_5") (pintype "passive"))
      (node (ref "T6") (pin "1") (pinfunction "NC_1") (pintype "passive"))
      (node (ref "T6") (pin "2") (pinfunction "2_2") (pintype "passive"))
      (node (ref "T6") (pin "5") (pinfunction "NC_5") (pintype "passive"))
      (node (ref "VD1") (pin "2") (pinfunction "2_2") (pintype "passive"))
      (node (ref "VD10") (pin "2") (pinfunction "2_2") (pintype "passive"))
      (node (ref "VD2") (pin "2") (pinfunction "2_2") (pintype "passive"))
      (node (ref "VD3") (pin "2") (pinfunction "2_2") (pintype "passive"))
      (node (ref "VD4") (pin "2") (pinfunction "2_2") (pintype "passive"))
      (node (ref "VD5") (pin "2") (pinfunction "2_2") (pintype "passive"))
      (node (ref "VD6") (pin "2") (pinfunction "2_2") (pintype "passive"))
      (node (ref "VD7") (pin "2") (pinfunction "2_2") (pintype "passive"))
      (node (ref "VD8") (pin "2") (pinfunction "2_2") (pintype "passive"))
      (node (ref "VD9") (pin "2") (pinfunction "2_2") (pintype "passive"))
      (node (ref "XW1") (pin "2") (pinfunction "2_2") (pintype "passive"))
      (node (ref "XW10") (pin "2") (pinfunction "2_2") (pintype "passive"))
      (node (ref "XW2") (pin "2") (pinfunction "2_2") (pintype "passive"))
      (node (ref "XW3") (pin "2") (pinfunction "2_2") (pintype "passive"))
      (node (ref "XW4") (pin "2") (pinfunction "2_2") (pintype "passive"))
      (node (ref "XW5") (pin "2") (pinfunction "2_2") (pintype "passive"))
      (node (ref "XW6") (pin "2") (pinfunction "2_2") (pintype "passive"))
      (node (ref "XW7") (pin "2") (pinfunction "2_2") (pintype "passive"))
      (node (ref "XW8") (pin "2") (pinfunction "2_2") (pintype "passive"))
      (node (ref "XW9") (pin "2") (pinfunction "2_2") (pintype "passive"))
    )
    (net (code "99") (name "Net-(C10-Pad1)") (class "Default")
      (node (ref "C10") (pin "1") (pinfunction "1_1") (pintype "passive"))
      (node (ref "C12") (pin "1") (pinfunction "1_1") (pintype "passive"))
      (node (ref "C14") (pin "1") (pinfunction "1_1") (pintype "passive"))
      (node (ref "L2") (pin "2") (pinfunction "2_2") (pintype "passive"))
      (node (ref "L4") (pin "2") (pinfunction "2_2") (pintype "passive"))
      (node (ref "L8") (pin "1") (pinfunction "1_1") (pintype "passive"))
    )
    (net (code "100") (name "Net-(C11-Pad1)") (class "Default")
      (node (ref "C11") (pin "1") (pinfunction "1_1") (pintype "passive"))
      (node (ref "C13") (pin "1") (pinfunction "1_1") (pintype "passive"))
      (node (ref "C9") (pin "1") (pinfunction "1_1") (pintype "passive"))
      (node (ref "L1") (pin "2") (pinfunction "2_2") (pintype "passive"))
      (node (ref "L3") (pin "2") (pinfunction "2_2") (pintype "passive"))
      (node (ref "L7") (pin "1") (pinfunction "1_1") (pintype "passive"))
    )
    (net (code "101") (name "Net-(C19-Pad2)") (class "Default")
      (node (ref "C19") (pin "2") (pinfunction "2_2") (pintype "passive"))
      (node (ref "R1") (pin "1") (pinfunction "1_1") (pintype "passive"))
      (node (ref "R7") (pin "1") (pinfunction "1_1") (pintype "passive"))
    )
    (net (code "102") (name "Net-(C26-Pad1)") (class "Default")
      (node (ref "C26") (pin "1") (pinfunction "1_1") (pintype "passive"))
      (node (ref "R28") (pin "2") (pinfunction "2_2") (pintype "passive"))
      (node (ref "R29") (pin "1") (pinfunction "1_1") (pintype "passive"))
    )
    (net (code "103") (name "Net-(C29-Pad2)") (class "Default")
      (node (ref "C29") (pin "2") (pinfunction "2_2") (pintype "passive"))
      (node (ref "R8") (pin "2") (pinfunction "2_2") (pintype "passive"))
      (node (ref "R9") (pin "1") (pinfunction "1_1") (pintype "passive"))
    )
    (net (code "104") (name "Net-(C32-Pad1)") (class "Default")
      (node (ref "C32") (pin "1") (pinfunction "1_1") (pintype "passive"))
      (node (ref "R11") (pin "2") (pinfunction "2_2") (pintype "passive"))
    )
    (net (code "105") (name "Net-(DD1-FILTA)") (class "Default")
      (node (ref "DD1") (pin "1") (pinfunction "FILTA_1") (pintype "passive"))
      (node (ref "R2") (pin "2") (pinfunction "2_2") (pintype "passive"))
      (node (ref "R3") (pin "1") (pinfunction "1_1") (pintype "passive"))
    )
    (net (code "106") (name "Net-(DD1-FILTB)") (class "Default")
      (node (ref "DD1") (pin "6") (pinfunction "FILTB_6") (pintype "passive"))
      (node (ref "R5") (pin "2") (pinfunction "2_2") (pintype "passive"))
      (node (ref "R6") (pin "1") (pinfunction "1_1") (pintype "passive"))
    )
    (net (code "107") (name "Net-(DD1-IN+)") (class "Default")
      (node (ref "DD1") (pin "3") (pinfunction "IN+_3") (pintype "passive"))
      (node (ref "R7") (pin "2") (pinfunction "2_2") (pintype "passive"))
    )
    (net (code "108") (name "Net-(DD1-IN-)") (class "Default")
      (node (ref "C22") (pin "1") (pinfunction "1_1") (pintype "passive"))
      (node (ref "DD1") (pin "4") (pinfunction "IN-_4") (pintype "passive"))
      (node (ref "R1") (pin "2") (pinfunction "2_2") (pintype "passive"))
    )
    (net (code "109") (name "Net-(DD1-OUT1)") (class "Default")
      (node (ref "DD1") (pin "10") (pinfunction "OUT1_10") (pintype "passive"))
      (node (ref "R8") (pin "1") (pinfunction "1_1") (pintype "passive"))
    )
    (net (code "110") (name "Net-(DD1-OUT2)") (class "Default")
      (node (ref "DD1") (pin "9") (pinfunction "OUT2_9") (pintype "passive"))
      (node (ref "R10") (pin "1") (pinfunction "1_1") (pintype "passive"))
    )
    (net (code "111") (name "Net-(DD1-V+)") (class "Default")
      (node (ref "C28") (pin "1") (pinfunction "1_1") (pintype "passive"))
      (node (ref "C30") (pin "1") (pinfunction "1_1") (pintype "passive"))
      (node (ref "C31") (pin "1") (pinfunction "1_1") (pintype "passive"))
      (node (ref "DD1") (pin "11") (pinfunction "VDD_11") (pintype "passive"))
      (node (ref "DD1") (pin "2") (pinfunction "V+_2") (pintype "passive"))
      (node (ref "L6") (pin "1") (pinfunction "1_1") (pintype "passive"))
    )
    (net (code "112") (name "Net-(G1-OE{slash}nST)") (class "Default")
      (node (ref "C24") (pin "1") (pinfunction "1_1") (pintype "passive"))
      (node (ref "G1") (pin "1") (pinfunction "OE/nST_1") (pintype "passive"))
      (node (ref "R4") (pin "2") (pinfunction "2_2") (pintype "passive"))
    )
    (net (code "113") (name "Net-(G1-OUT)") (class "Default")
      (node (ref "G1") (pin "3") (pinfunction "OUT_3") (pintype "passive"))
      (node (ref "R28") (pin "1") (pinfunction "1_1") (pintype "passive"))
    )
    (net (code "114") (name "Net-(G1-VDD)") (class "Default")
      (node (ref "C21") (pin "1") (pinfunction "1_1") (pintype "passive"))
      (node (ref "C23") (pin "1") (pinfunction "1_1") (pintype "passive"))
      (node (ref "G1") (pin "4") (pinfunction "VDD_4") (pintype "passive"))
      (node (ref "L5") (pin "2") (pinfunction "2_2") (pintype "passive"))
    )
    (net (code "115") (name "unconnected-(DA1C-DNC-PadA3)") (class "Default")
      (node (ref "DA1") (pin "A3") (pinfunction "DNC_A3") (pintype "passive"))
    )
    (net (code "116") (name "unconnected-(DA1C-DNC-PadM3)") (class "Default")
      (node (ref "DA1") (pin "M3") (pinfunction "DNC_M3") (pintype "passive"))
    )
    (net (code "117") (name "unconnected-(DA1C-DNC-PadM11)") (class "Default")
      (node (ref "DA1") (pin "M11") (pinfunction "DNC_M11") (pintype "passive"))
    )
  )
)
